# expansion.net
KiCad netlist of a schematic drawn in EAGLE
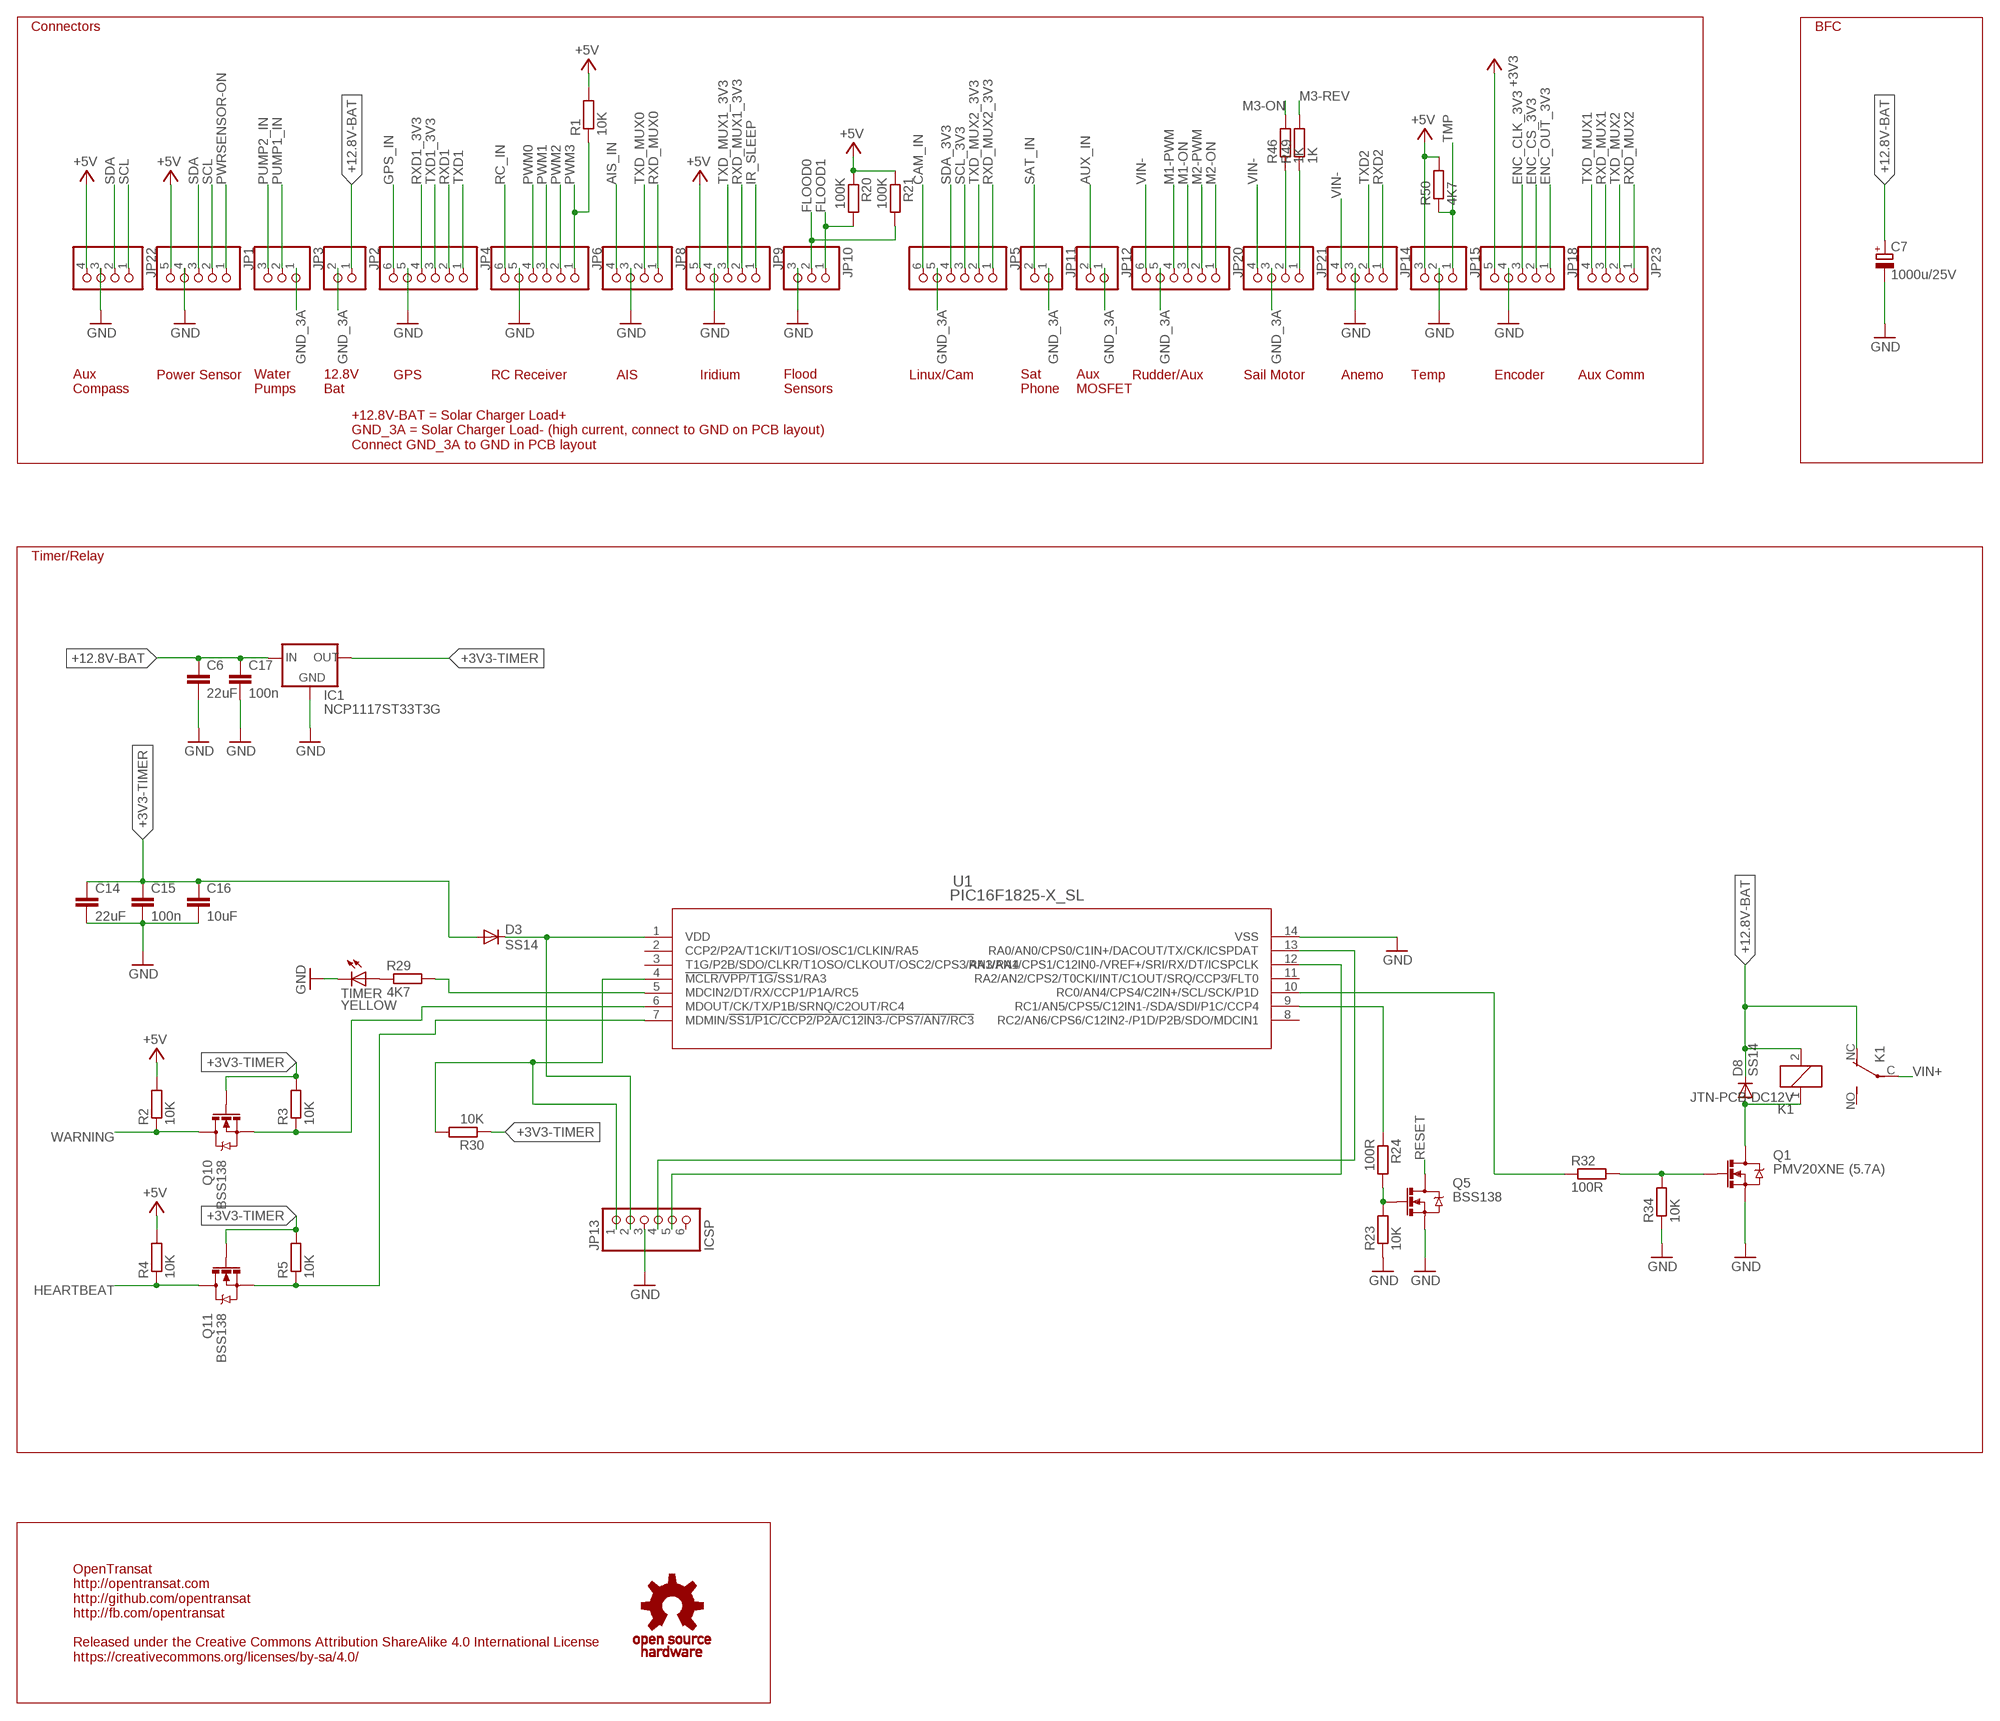
[diagram p0: schematic, sheet 1, part 1 of 2]
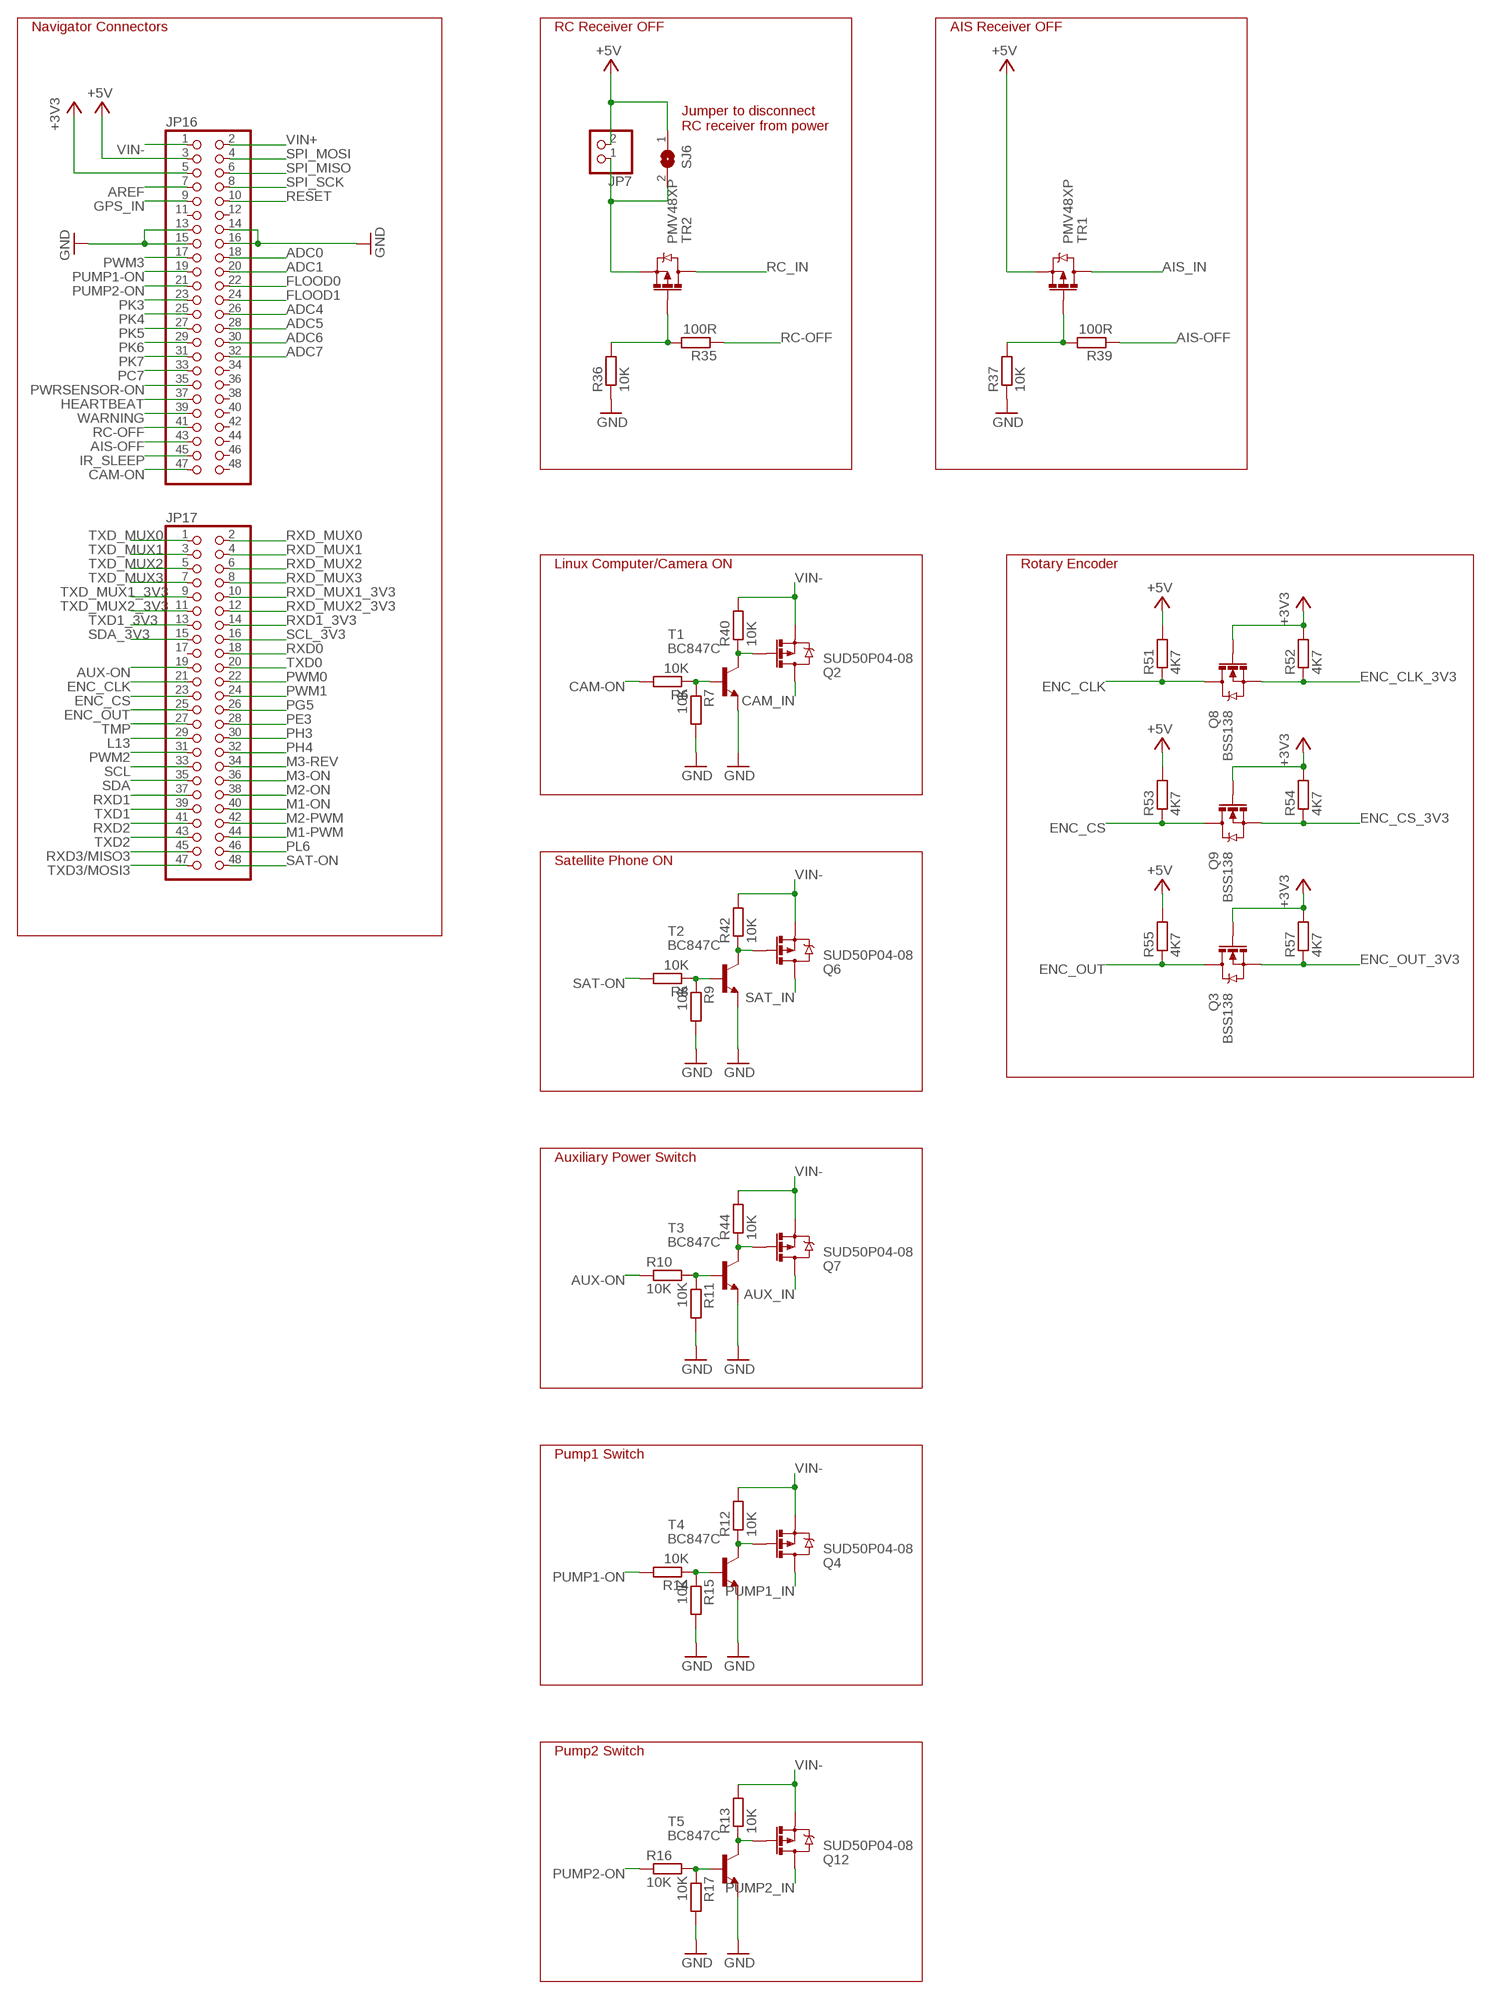
[diagram p1: schematic, sheet 1, part 2 of 2]

(export (version "E")
  (design (tool "Eeschema 10.0.6"))
  (components
    (comp (ref "C6")
      (value "22uF")
      (footprint "eagle-import:C1210")
      (libsource (lib "eagle-import") (part "C-EUC1210"))
    )
    (comp (ref "C7")
      (value "1000u/25V")
      (footprint "eagle-import:E5-10,5")
      (libsource (lib "eagle-import") (part "CPOL-EUE5-10.5"))
    )
    (comp (ref "C14")
      (value "22uF")
      (footprint "eagle-import:C1210")
      (libsource (lib "eagle-import") (part "C-EUC1210"))
    )
    (comp (ref "C15")
      (value "100n")
      (footprint "eagle-import:C0603")
      (libsource (lib "eagle-import") (part "C-EUC0603"))
    )
    (comp (ref "C16")
      (value "10uF")
      (footprint "eagle-import:C1206")
      (libsource (lib "eagle-import") (part "C-EUC1206"))
    )
    (comp (ref "C17")
      (value "100n")
      (footprint "eagle-import:C0603")
      (libsource (lib "eagle-import") (part "C-EUC0603"))
    )
    (comp (ref "D3")
      (value "SS14")
      (footprint "eagle-import:DO214AC")
      (libsource (lib "eagle-import") (part "DIODE-DO214AC"))
    )
    (comp (ref "D8")
      (value "SS14")
      (footprint "eagle-import:DO214AC")
      (libsource (lib "eagle-import") (part "DIODE-DO214AC"))
    )
    (comp (ref "IC1")
      (value "NCP1117ST33T3G")
      (footprint "eagle-import:SOT223")
      (fields (field (name "MF") "Texas Instruments") (field (name "MPN") "LM1117MP-3.3"))
      (libsource (lib "eagle-import") (part "LM1117?-MP3.3"))
    )
    (comp (ref "JP1")
      (value "PINHD-1X5")
      (footprint "eagle-import:1X05")
      (libsource (lib "eagle-import") (part "PINHD-1X5"))
    )
    (comp (ref "JP2")
      (value "PINHD-1X2")
      (footprint "eagle-import:1X02")
      (libsource (lib "eagle-import") (part "PINHD-1X2"))
    )
    (comp (ref "JP3")
      (value "PINHD-1X3")
      (footprint "eagle-import:1X03")
      (libsource (lib "eagle-import") (part "PINHD-1X3"))
    )
    (comp (ref "JP4")
      (value "PINHD-1X6")
      (footprint "eagle-import:1X06")
      (libsource (lib "eagle-import") (part "PINHD-1X6"))
    )
    (comp (ref "JP5")
      (value "PINHD-1X6")
      (footprint "eagle-import:1X06")
      (libsource (lib "eagle-import") (part "PINHD-1X6"))
    )
    (comp (ref "JP6")
      (value "PINHD-1X6")
      (footprint "eagle-import:1X06")
      (libsource (lib "eagle-import") (part "PINHD-1X6"))
    )
    (comp (ref "JP7")
      (value "PINHD-1X2")
      (footprint "eagle-import:1X02")
      (libsource (lib "eagle-import") (part "PINHD-1X2"))
    )
    (comp (ref "JP8")
      (value "PINHD-1X4")
      (footprint "eagle-import:1X04")
      (libsource (lib "eagle-import") (part "PINHD-1X4"))
    )
    (comp (ref "JP9")
      (value "PINHD-1X5")
      (footprint "eagle-import:1X05")
      (libsource (lib "eagle-import") (part "PINHD-1X5"))
    )
    (comp (ref "JP10")
      (value "PINHD-1X3")
      (footprint "eagle-import:1X03")
      (libsource (lib "eagle-import") (part "PINHD-1X3"))
    )
    (comp (ref "JP11")
      (value "PINHD-1X2")
      (footprint "eagle-import:1X02")
      (libsource (lib "eagle-import") (part "PINHD-1X2"))
    )
    (comp (ref "JP12")
      (value "PINHD-1X2")
      (footprint "eagle-import:1X02")
      (libsource (lib "eagle-import") (part "PINHD-1X2"))
    )
    (comp (ref "JP13")
      (value "ICSP")
      (footprint "eagle-import:1X06")
      (libsource (lib "eagle-import") (part "PINHD-1X6"))
    )
    (comp (ref "JP14")
      (value "PINHD-1X4")
      (footprint "eagle-import:1X04")
      (libsource (lib "eagle-import") (part "PINHD-1X4"))
    )
    (comp (ref "JP15")
      (value "PINHD-1X3")
      (footprint "eagle-import:1X03")
      (libsource (lib "eagle-import") (part "PINHD-1X3"))
    )
    (comp (ref "JP16")
      (value "PINHD-2X24")
      (footprint "eagle-import:2X24")
      (libsource (lib "eagle-import") (part "PINHD-2X24"))
    )
    (comp (ref "JP17")
      (value "PINHD-2X24")
      (footprint "eagle-import:2X24")
      (libsource (lib "eagle-import") (part "PINHD-2X24"))
    )
    (comp (ref "JP18")
      (value "PINHD-1X5")
      (footprint "eagle-import:1X05")
      (libsource (lib "eagle-import") (part "PINHD-1X5"))
    )
    (comp (ref "JP20")
      (value "PINHD-1X6")
      (footprint "eagle-import:1X06")
      (libsource (lib "eagle-import") (part "PINHD-1X6"))
    )
    (comp (ref "JP21")
      (value "PINHD-1X4")
      (footprint "eagle-import:1X04")
      (libsource (lib "eagle-import") (part "PINHD-1X4"))
    )
    (comp (ref "JP22")
      (value "PINHD-1X4")
      (footprint "eagle-import:1X04")
      (libsource (lib "eagle-import") (part "PINHD-1X4"))
    )
    (comp (ref "JP23")
      (value "PINHD-1X4")
      (footprint "eagle-import:1X04")
      (libsource (lib "eagle-import") (part "PINHD-1X4"))
    )
    (comp (ref "K1")
      (value "JTN-PCB-DC12V")
      (footprint "eagle-import:JT-PCB")
      (libsource (lib "eagle-import") (part "JT?-N-PCBDC12V"))
    )
    (comp (ref "Q1")
      (value "PMV20XNE (5.7A)")
      (footprint "eagle-import:SOT23-3")
      (libsource (lib "eagle-import") (part "MOSFET-NCHANNEL_SOT23-3"))
    )
    (comp (ref "Q2")
      (value "SUD50P04-08")
      (footprint "eagle-import:D-PAK_TO252AA")
      (libsource (lib "eagle-import") (part "MOSFET-PCHANNEL_D-PAK"))
    )
    (comp (ref "Q3")
      (value "BSS138")
      (footprint "eagle-import:SOT23-3")
      (libsource (lib "eagle-import") (part "MOSFET-NCHANNEL_SOT23-3"))
    )
    (comp (ref "Q4")
      (value "SUD50P04-08")
      (footprint "eagle-import:D-PAK_TO252AA")
      (libsource (lib "eagle-import") (part "MOSFET-PCHANNEL_D-PAK"))
    )
    (comp (ref "Q5")
      (value "BSS138")
      (footprint "eagle-import:SOT23-3")
      (libsource (lib "eagle-import") (part "MOSFET-NCHANNEL_SOT23-3"))
    )
    (comp (ref "Q6")
      (value "SUD50P04-08")
      (footprint "eagle-import:D-PAK_TO252AA")
      (libsource (lib "eagle-import") (part "MOSFET-PCHANNEL_D-PAK"))
    )
    (comp (ref "Q7")
      (value "SUD50P04-08")
      (footprint "eagle-import:D-PAK_TO252AA")
      (libsource (lib "eagle-import") (part "MOSFET-PCHANNEL_D-PAK"))
    )
    (comp (ref "Q8")
      (value "BSS138")
      (footprint "eagle-import:SOT23-3")
      (libsource (lib "eagle-import") (part "MOSFET-NCHANNEL_SOT23-3"))
    )
    (comp (ref "Q9")
      (value "BSS138")
      (footprint "eagle-import:SOT23-3")
      (libsource (lib "eagle-import") (part "MOSFET-NCHANNEL_SOT23-3"))
    )
    (comp (ref "Q10")
      (value "BSS138")
      (footprint "eagle-import:SOT23-3")
      (libsource (lib "eagle-import") (part "MOSFET-NCHANNEL_SOT23-3"))
    )
    (comp (ref "Q11")
      (value "BSS138")
      (footprint "eagle-import:SOT23-3")
      (libsource (lib "eagle-import") (part "MOSFET-NCHANNEL_SOT23-3"))
    )
    (comp (ref "Q12")
      (value "SUD50P04-08")
      (footprint "eagle-import:D-PAK_TO252AA")
      (libsource (lib "eagle-import") (part "MOSFET-PCHANNEL_D-PAK"))
    )
    (comp (ref "R1")
      (value "10K")
      (footprint "eagle-import:R0603")
      (libsource (lib "eagle-import") (part "R-EU_R0603"))
    )
    (comp (ref "R2")
      (value "10K")
      (footprint "eagle-import:R0603")
      (libsource (lib "eagle-import") (part "R-EU_R0603"))
    )
    (comp (ref "R3")
      (value "10K")
      (footprint "eagle-import:R0603")
      (libsource (lib "eagle-import") (part "R-EU_R0603"))
    )
    (comp (ref "R4")
      (value "10K")
      (footprint "eagle-import:R0603")
      (libsource (lib "eagle-import") (part "R-EU_R0603"))
    )
    (comp (ref "R5")
      (value "10K")
      (footprint "eagle-import:R0603")
      (libsource (lib "eagle-import") (part "R-EU_R0603"))
    )
    (comp (ref "R6")
      (value "10K")
      (footprint "eagle-import:R0603")
      (libsource (lib "eagle-import") (part "R-EU_R0603"))
    )
    (comp (ref "R7")
      (value "10K")
      (footprint "eagle-import:R0603")
      (libsource (lib "eagle-import") (part "R-EU_R0603"))
    )
    (comp (ref "R8")
      (value "10K")
      (footprint "eagle-import:R0603")
      (libsource (lib "eagle-import") (part "R-EU_R0603"))
    )
    (comp (ref "R9")
      (value "10K")
      (footprint "eagle-import:R0603")
      (libsource (lib "eagle-import") (part "R-EU_R0603"))
    )
    (comp (ref "R10")
      (value "10K")
      (footprint "eagle-import:R0603")
      (libsource (lib "eagle-import") (part "R-EU_R0603"))
    )
    (comp (ref "R11")
      (value "10K")
      (footprint "eagle-import:R0603")
      (libsource (lib "eagle-import") (part "R-EU_R0603"))
    )
    (comp (ref "R12")
      (value "10K")
      (footprint "eagle-import:R0603")
      (libsource (lib "eagle-import") (part "R-EU_R0603"))
    )
    (comp (ref "R13")
      (value "10K")
      (footprint "eagle-import:R0603")
      (libsource (lib "eagle-import") (part "R-EU_R0603"))
    )
    (comp (ref "R14")
      (value "10K")
      (footprint "eagle-import:R0603")
      (libsource (lib "eagle-import") (part "R-EU_R0603"))
    )
    (comp (ref "R15")
      (value "10K")
      (footprint "eagle-import:R0603")
      (libsource (lib "eagle-import") (part "R-EU_R0603"))
    )
    (comp (ref "R16")
      (value "10K")
      (footprint "eagle-import:R0603")
      (libsource (lib "eagle-import") (part "R-EU_R0603"))
    )
    (comp (ref "R17")
      (value "10K")
      (footprint "eagle-import:R0603")
      (libsource (lib "eagle-import") (part "R-EU_R0603"))
    )
    (comp (ref "R20")
      (value "100K")
      (footprint "eagle-import:R0603")
      (libsource (lib "eagle-import") (part "R-EU_R0603"))
    )
    (comp (ref "R21")
      (value "100K")
      (footprint "eagle-import:R0603")
      (libsource (lib "eagle-import") (part "R-EU_R0603"))
    )
    (comp (ref "R23")
      (value "10K")
      (footprint "eagle-import:R0603")
      (libsource (lib "eagle-import") (part "R-EU_R0603"))
    )
    (comp (ref "R24")
      (value "100R")
      (footprint "eagle-import:R0603")
      (libsource (lib "eagle-import") (part "R-EU_R0603"))
    )
    (comp (ref "R29")
      (value "4K7")
      (footprint "eagle-import:R0603")
      (libsource (lib "eagle-import") (part "R-EU_R0603"))
    )
    (comp (ref "R30")
      (value "10K")
      (footprint "eagle-import:R0603")
      (libsource (lib "eagle-import") (part "R-EU_R0603"))
    )
    (comp (ref "R32")
      (value "100R")
      (footprint "eagle-import:R0603")
      (libsource (lib "eagle-import") (part "R-EU_R0603"))
    )
    (comp (ref "R34")
      (value "10K")
      (footprint "eagle-import:R0603")
      (libsource (lib "eagle-import") (part "R-EU_R0603"))
    )
    (comp (ref "R35")
      (value "100R")
      (footprint "eagle-import:R0603")
      (libsource (lib "eagle-import") (part "R-EU_R0603"))
    )
    (comp (ref "R36")
      (value "10K")
      (footprint "eagle-import:R0603")
      (libsource (lib "eagle-import") (part "R-EU_R0603"))
    )
    (comp (ref "R37")
      (value "10K")
      (footprint "eagle-import:R0603")
      (libsource (lib "eagle-import") (part "R-EU_R0603"))
    )
    (comp (ref "R39")
      (value "100R")
      (footprint "eagle-import:R0603")
      (libsource (lib "eagle-import") (part "R-EU_R0603"))
    )
    (comp (ref "R40")
      (value "10K")
      (footprint "eagle-import:R0603")
      (libsource (lib "eagle-import") (part "R-EU_R0603"))
    )
    (comp (ref "R42")
      (value "10K")
      (footprint "eagle-import:R0603")
      (libsource (lib "eagle-import") (part "R-EU_R0603"))
    )
    (comp (ref "R44")
      (value "10K")
      (footprint "eagle-import:R0603")
      (libsource (lib "eagle-import") (part "R-EU_R0603"))
    )
    (comp (ref "R46")
      (value "1K")
      (footprint "eagle-import:R0603")
      (libsource (lib "eagle-import") (part "R-EU_R0603"))
    )
    (comp (ref "R49")
      (value "1K")
      (footprint "eagle-import:R0603")
      (libsource (lib "eagle-import") (part "R-EU_R0603"))
    )
    (comp (ref "R50")
      (value "4K7")
      (footprint "eagle-import:R0603")
      (libsource (lib "eagle-import") (part "R-EU_R0603"))
    )
    (comp (ref "R51")
      (value "4K7")
      (footprint "eagle-import:R0603")
      (libsource (lib "eagle-import") (part "R-EU_R0603"))
    )
    (comp (ref "R52")
      (value "4K7")
      (footprint "eagle-import:R0603")
      (libsource (lib "eagle-import") (part "R-EU_R0603"))
    )
    (comp (ref "R53")
      (value "4K7")
      (footprint "eagle-import:R0603")
      (libsource (lib "eagle-import") (part "R-EU_R0603"))
    )
    (comp (ref "R54")
      (value "4K7")
      (footprint "eagle-import:R0603")
      (libsource (lib "eagle-import") (part "R-EU_R0603"))
    )
    (comp (ref "R55")
      (value "4K7")
      (footprint "eagle-import:R0603")
      (libsource (lib "eagle-import") (part "R-EU_R0603"))
    )
    (comp (ref "R57")
      (value "4K7")
      (footprint "eagle-import:R0603")
      (libsource (lib "eagle-import") (part "R-EU_R0603"))
    )
    (comp (ref "SJ6") (value "SJ") (footprint "eagle-import:SJ") (libsource (lib "eagle-import") (part "SJ")))
    (comp (ref "T1")
      (value "BC847C")
      (footprint "eagle-import:SOT23")
      (libsource (lib "eagle-import") (part "BC847"))
    )
    (comp (ref "T2")
      (value "BC847C")
      (footprint "eagle-import:SOT23")
      (libsource (lib "eagle-import") (part "BC847"))
    )
    (comp (ref "T3")
      (value "BC847C")
      (footprint "eagle-import:SOT23")
      (libsource (lib "eagle-import") (part "BC847"))
    )
    (comp (ref "T4")
      (value "BC847C")
      (footprint "eagle-import:SOT23")
      (libsource (lib "eagle-import") (part "BC847"))
    )
    (comp (ref "T5")
      (value "BC847C")
      (footprint "eagle-import:SOT23")
      (libsource (lib "eagle-import") (part "BC847"))
    )
    (comp (ref "TIMER")
      (value "YELLOW")
      (footprint "eagle-import:CHIPLED_0805")
      (libsource (lib "eagle-import") (part "LEDCHIPLED_0805"))
    )
    (comp (ref "TR1")
      (value "PMV48XP")
      (footprint "eagle-import:SOT23-3")
      (libsource (lib "eagle-import") (part "MOSFET-PCHANNEL_SOT23-3"))
    )
    (comp (ref "TR2")
      (value "PMV48XP")
      (footprint "eagle-import:SOT23-3")
      (libsource (lib "eagle-import") (part "MOSFET-PCHANNEL_SOT23-3"))
    )
    (comp (ref "U$2")
      (value "OSHW")
      (footprint "eagle-import:OSHWM")
      (libsource (lib "eagle-import") (part "OSHW"))
    )
    (comp (ref "U1")
      (value "PIC16F1825-X_SL")
      (footprint "eagle-import:SOIC14-N_MC")
      (libsource (lib "eagle-import") (part "PIC16F1825-X_SL"))
    )
  )
  (nets
    (net (code "1") (name "+3V3") (class "Default")
      (node (ref "JP16") (pin "5") (pinfunction "5_5") (pintype "passive"))
      (node (ref "JP18") (pin "5") (pinfunction "5_5") (pintype "passive"))
      (node (ref "Q3") (pin "1") (pinfunction "G_1") (pintype "passive"))
      (node (ref "Q8") (pin "1") (pinfunction "G_1") (pintype "passive"))
      (node (ref "Q9") (pin "1") (pinfunction "G_1") (pintype "passive"))
      (node (ref "R52") (pin "2") (pinfunction "2_2") (pintype "passive"))
      (node (ref "R54") (pin "2") (pinfunction "2_2") (pintype "passive"))
      (node (ref "R57") (pin "2") (pinfunction "2_2") (pintype "passive"))
    )
    (net (code "2") (name "+3V3-TIMER") (class "Default")
      (node (ref "C14") (pin "1") (pinfunction "1_1") (pintype "passive"))
      (node (ref "C15") (pin "1") (pinfunction "1_1") (pintype "passive"))
      (node (ref "C16") (pin "1") (pinfunction "1_1") (pintype "passive"))
      (node (ref "D3") (pin "A") (pinfunction "A_A") (pintype "passive"))
      (node (ref "IC1") (pin "2") (pinfunction "OUT_2") (pintype "passive"))
      (node (ref "IC1") (pin "4") (pinfunction "OUT_4") (pintype "passive"))
      (node (ref "Q10") (pin "1") (pinfunction "G_1") (pintype "passive"))
      (node (ref "Q11") (pin "1") (pinfunction "G_1") (pintype "passive"))
      (node (ref "R3") (pin "2") (pinfunction "2_2") (pintype "passive"))
      (node (ref "R30") (pin "1") (pinfunction "1_1") (pintype "passive"))
      (node (ref "R5") (pin "2") (pinfunction "2_2") (pintype "passive"))
    )
    (net (code "3") (name "+5V") (class "Default")
      (node (ref "JP1") (pin "5") (pinfunction "5_5") (pintype "passive"))
      (node (ref "JP15") (pin "3") (pinfunction "3_3") (pintype "passive"))
      (node (ref "JP16") (pin "3") (pinfunction "3_3") (pintype "passive"))
      (node (ref "JP22") (pin "4") (pinfunction "4_4") (pintype "passive"))
      (node (ref "JP7") (pin "2") (pinfunction "2_2") (pintype "passive"))
      (node (ref "JP9") (pin "5") (pinfunction "5_5") (pintype "passive"))
      (node (ref "R1") (pin "2") (pinfunction "2_2") (pintype "passive"))
      (node (ref "R2") (pin "2") (pinfunction "2_2") (pintype "passive"))
      (node (ref "R20") (pin "1") (pinfunction "1_1") (pintype "passive"))
      (node (ref "R21") (pin "1") (pinfunction "1_1") (pintype "passive"))
      (node (ref "R4") (pin "2") (pinfunction "2_2") (pintype "passive"))
      (node (ref "R50") (pin "2") (pinfunction "2_2") (pintype "passive"))
      (node (ref "R51") (pin "2") (pinfunction "2_2") (pintype "passive"))
      (node (ref "R53") (pin "2") (pinfunction "2_2") (pintype "passive"))
      (node (ref "R55") (pin "2") (pinfunction "2_2") (pintype "passive"))
      (node (ref "SJ6") (pin "1") (pinfunction "1_1") (pintype "passive"))
      (node (ref "TR1") (pin "2") (pinfunction "S_2") (pintype "passive"))
    )
    (net (code "4") (name "+12.8V-BAT") (class "Default")
      (node (ref "C17") (pin "1") (pinfunction "1_1") (pintype "passive"))
      (node (ref "C6") (pin "1") (pinfunction "1_1") (pintype "passive"))
      (node (ref "C7") (pin "+") (pinfunction "+_+") (pintype "passive"))
      (node (ref "D8") (pin "C") (pinfunction "C_C") (pintype "passive"))
      (node (ref "IC1") (pin "3") (pinfunction "IN_3") (pintype "input"))
      (node (ref "JP2") (pin "1") (pinfunction "1_1") (pintype "passive"))
      (node (ref "K1") (pin "2") (pinfunction "2_2") (pintype "passive"))
      (node (ref "K1") (pin "NC") (pinfunction "O_NC") (pintype "passive"))
    )
    (net (code "5") (name "/ADC0") (class "Default")
      (node (ref "JP16") (pin "18") (pinfunction "18_18") (pintype "passive"))
    )
    (net (code "6") (name "/ADC1") (class "Default")
      (node (ref "JP16") (pin "20") (pinfunction "20_20") (pintype "passive"))
    )
    (net (code "7") (name "/ADC4") (class "Default")
      (node (ref "JP16") (pin "26") (pinfunction "26_26") (pintype "passive"))
    )
    (net (code "8") (name "/ADC5") (class "Default")
      (node (ref "JP16") (pin "28") (pinfunction "28_28") (pintype "passive"))
    )
    (net (code "9") (name "/ADC6") (class "Default")
      (node (ref "JP16") (pin "30") (pinfunction "30_30") (pintype "passive"))
    )
    (net (code "10") (name "/ADC7") (class "Default")
      (node (ref "JP16") (pin "32") (pinfunction "32_32") (pintype "passive"))
    )
    (net (code "11") (name "/AIS-OFF") (class "Default")
      (node (ref "JP16") (pin "43") (pinfunction "43_43") (pintype "passive"))
      (node (ref "R39") (pin "1") (pinfunction "1_1") (pintype "passive"))
    )
    (net (code "12") (name "/AIS_IN") (class "Default")
      (node (ref "JP8") (pin "4") (pinfunction "4_4") (pintype "passive"))
      (node (ref "TR1") (pin "3") (pinfunction "D_3") (pintype "passive"))
    )
    (net (code "13") (name "/AREF") (class "Default")
      (node (ref "JP16") (pin "7") (pinfunction "7_7") (pintype "passive"))
    )
    (net (code "14") (name "/AUX-ON") (class "Default")
      (node (ref "JP17") (pin "19") (pinfunction "19_19") (pintype "passive"))
      (node (ref "R10") (pin "1") (pinfunction "1_1") (pintype "passive"))
    )
    (net (code "15") (name "/AUX_IN") (class "Default")
      (node (ref "JP12") (pin "2") (pinfunction "2_2") (pintype "passive"))
      (node (ref "Q7") (pin "2") (pinfunction "D_2") (pintype "passive"))
    )
    (net (code "16") (name "/CAM-ON") (class "Default")
      (node (ref "JP16") (pin "47") (pinfunction "47_47") (pintype "passive"))
      (node (ref "R6") (pin "2") (pinfunction "2_2") (pintype "passive"))
    )
    (net (code "17") (name "/CAM_IN") (class "Default")
      (node (ref "JP5") (pin "6") (pinfunction "6_6") (pintype "passive"))
      (node (ref "Q2") (pin "2") (pinfunction "D_2") (pintype "passive"))
    )
    (net (code "18") (name "/ENC_CLK") (class "Default")
      (node (ref "JP17") (pin "21") (pinfunction "21_21") (pintype "passive"))
      (node (ref "Q8") (pin "3") (pinfunction "D_3") (pintype "passive"))
      (node (ref "R51") (pin "1") (pinfunction "1_1") (pintype "passive"))
    )
    (net (code "19") (name "/ENC_CLK_3V3") (class "Default")
      (node (ref "JP18") (pin "3") (pinfunction "3_3") (pintype "passive"))
      (node (ref "Q8") (pin "2") (pinfunction "S_2") (pintype "passive"))
      (node (ref "R52") (pin "1") (pinfunction "1_1") (pintype "passive"))
    )
    (net (code "20") (name "/ENC_CS") (class "Default")
      (node (ref "JP17") (pin "23") (pinfunction "23_23") (pintype "passive"))
      (node (ref "Q9") (pin "3") (pinfunction "D_3") (pintype "passive"))
      (node (ref "R53") (pin "1") (pinfunction "1_1") (pintype "passive"))
    )
    (net (code "21") (name "/ENC_CS_3V3") (class "Default")
      (node (ref "JP18") (pin "2") (pinfunction "2_2") (pintype "passive"))
      (node (ref "Q9") (pin "2") (pinfunction "S_2") (pintype "passive"))
      (node (ref "R54") (pin "1") (pinfunction "1_1") (pintype "passive"))
    )
    (net (code "22") (name "/ENC_OUT") (class "Default")
      (node (ref "JP17") (pin "25") (pinfunction "25_25") (pintype "passive"))
      (node (ref "Q3") (pin "3") (pinfunction "D_3") (pintype "passive"))
      (node (ref "R55") (pin "1") (pinfunction "1_1") (pintype "passive"))
    )
    (net (code "23") (name "/ENC_OUT_3V3") (class "Default")
      (node (ref "JP18") (pin "1") (pinfunction "1_1") (pintype "passive"))
      (node (ref "Q3") (pin "2") (pinfunction "S_2") (pintype "passive"))
      (node (ref "R57") (pin "1") (pinfunction "1_1") (pintype "passive"))
    )
    (net (code "24") (name "/FLOOD0") (class "Default")
      (node (ref "JP10") (pin "2") (pinfunction "2_2") (pintype "passive"))
      (node (ref "JP16") (pin "22") (pinfunction "22_22") (pintype "passive"))
      (node (ref "R21") (pin "2") (pinfunction "2_2") (pintype "passive"))
    )
    (net (code "25") (name "/FLOOD1") (class "Default")
      (node (ref "JP10") (pin "1") (pinfunction "1_1") (pintype "passive"))
      (node (ref "JP16") (pin "24") (pinfunction "24_24") (pintype "passive"))
      (node (ref "R20") (pin "2") (pinfunction "2_2") (pintype "passive"))
    )
    (net (code "26") (name "/GND_3A") (class "Default")
      (node (ref "JP11") (pin "1") (pinfunction "1_1") (pintype "passive"))
      (node (ref "JP12") (pin "1") (pinfunction "1_1") (pintype "passive"))
      (node (ref "JP2") (pin "2") (pinfunction "2_2") (pintype "passive"))
      (node (ref "JP20") (pin "5") (pinfunction "5_5") (pintype "passive"))
      (node (ref "JP21") (pin "3") (pinfunction "3_3") (pintype "passive"))
      (node (ref "JP3") (pin "1") (pinfunction "1_1") (pintype "passive"))
      (node (ref "JP5") (pin "5") (pinfunction "5_5") (pintype "passive"))
    )
    (net (code "27") (name "/GPS_IN") (class "Default")
      (node (ref "JP16") (pin "9") (pinfunction "9_9") (pintype "passive"))
      (node (ref "JP4") (pin "6") (pinfunction "6_6") (pintype "passive"))
    )
    (net (code "28") (name "/HEARTBEAT") (class "Default")
      (node (ref "JP16") (pin "37") (pinfunction "37_37") (pintype "passive"))
      (node (ref "Q11") (pin "3") (pinfunction "D_3") (pintype "passive"))
      (node (ref "R4") (pin "1") (pinfunction "1_1") (pintype "passive"))
    )
    (net (code "29") (name "/IR_SLEEP") (class "Default")
      (node (ref "JP16") (pin "45") (pinfunction "45_45") (pintype "passive"))
      (node (ref "JP9") (pin "1") (pinfunction "1_1") (pintype "passive"))
    )
    (net (code "30") (name "/L13") (class "Default")
      (node (ref "JP17") (pin "29") (pinfunction "29_29") (pintype "passive"))
    )
    (net (code "31") (name "/M1-ON") (class "Default")
      (node (ref "JP17") (pin "40") (pinfunction "40_40") (pintype "passive"))
      (node (ref "JP20") (pin "3") (pinfunction "3_3") (pintype "passive"))
    )
    (net (code "32") (name "/M1-PWM") (class "Default")
      (node (ref "JP17") (pin "44") (pinfunction "44_44") (pintype "passive"))
      (node (ref "JP20") (pin "4") (pinfunction "4_4") (pintype "passive"))
    )
    (net (code "33") (name "/M2-ON") (class "Default")
      (node (ref "JP17") (pin "38") (pinfunction "38_38") (pintype "passive"))
      (node (ref "JP20") (pin "1") (pinfunction "1_1") (pintype "passive"))
    )
    (net (code "34") (name "/M2-PWM") (class "Default")
      (node (ref "JP17") (pin "42") (pinfunction "42_42") (pintype "passive"))
      (node (ref "JP20") (pin "2") (pinfunction "2_2") (pintype "passive"))
    )
    (net (code "35") (name "/M3-ON") (class "Default")
      (node (ref "JP17") (pin "36") (pinfunction "36_36") (pintype "passive"))
      (node (ref "R46") (pin "2") (pinfunction "2_2") (pintype "passive"))
    )
    (net (code "36") (name "/M3-REV") (class "Default")
      (node (ref "JP17") (pin "34") (pinfunction "34_34") (pintype "passive"))
      (node (ref "R49") (pin "2") (pinfunction "2_2") (pintype "passive"))
    )
    (net (code "37") (name "/PC7") (class "Default")
      (node (ref "JP16") (pin "33") (pinfunction "33_33") (pintype "passive"))
    )
    (net (code "38") (name "/PE3") (class "Default")
      (node (ref "JP17") (pin "28") (pinfunction "28_28") (pintype "passive"))
    )
    (net (code "39") (name "/PG5") (class "Default")
      (node (ref "JP17") (pin "26") (pinfunction "26_26") (pintype "passive"))
    )
    (net (code "40") (name "/PH3") (class "Default")
      (node (ref "JP17") (pin "30") (pinfunction "30_30") (pintype "passive"))
    )
    (net (code "41") (name "/PH4") (class "Default")
      (node (ref "JP17") (pin "32") (pinfunction "32_32") (pintype "passive"))
    )
    (net (code "42") (name "/PK3") (class "Default")
      (node (ref "JP16") (pin "23") (pinfunction "23_23") (pintype "passive"))
    )
    (net (code "43") (name "/PK4") (class "Default")
      (node (ref "JP16") (pin "25") (pinfunction "25_25") (pintype "passive"))
    )
    (net (code "44") (name "/PK5") (class "Default")
      (node (ref "JP16") (pin "27") (pinfunction "27_27") (pintype "passive"))
    )
    (net (code "45") (name "/PK6") (class "Default")
      (node (ref "JP16") (pin "29") (pinfunction "29_29") (pintype "passive"))
    )
    (net (code "46") (name "/PK7") (class "Default")
      (node (ref "JP16") (pin "31") (pinfunction "31_31") (pintype "passive"))
    )
    (net (code "47") (name "/PL6") (class "Default")
      (node (ref "JP17") (pin "46") (pinfunction "46_46") (pintype "passive"))
    )
    (net (code "48") (name "/PUMP1-ON") (class "Default")
      (node (ref "JP16") (pin "19") (pinfunction "19_19") (pintype "passive"))
      (node (ref "R14") (pin "2") (pinfunction "2_2") (pintype "passive"))
    )
    (net (code "49") (name "/PUMP1_IN") (class "Default")
      (node (ref "JP3") (pin "2") (pinfunction "2_2") (pintype "passive"))
      (node (ref "Q4") (pin "2") (pinfunction "D_2") (pintype "passive"))
    )
    (net (code "50") (name "/PUMP2-ON") (class "Default")
      (node (ref "JP16") (pin "21") (pinfunction "21_21") (pintype "passive"))
      (node (ref "R16") (pin "1") (pinfunction "1_1") (pintype "passive"))
    )
    (net (code "51") (name "/PUMP2_IN") (class "Default")
      (node (ref "JP3") (pin "3") (pinfunction "3_3") (pintype "passive"))
      (node (ref "Q12") (pin "2") (pinfunction "D_2") (pintype "passive"))
    )
    (net (code "52") (name "/PWM0") (class "Default")
      (node (ref "JP17") (pin "22") (pinfunction "22_22") (pintype "passive"))
      (node (ref "JP6") (pin "4") (pinfunction "4_4") (pintype "passive"))
    )
    (net (code "53") (name "/PWM1") (class "Default")
      (node (ref "JP17") (pin "24") (pinfunction "24_24") (pintype "passive"))
      (node (ref "JP6") (pin "3") (pinfunction "3_3") (pintype "passive"))
    )
    (net (code "54") (name "/PWM2") (class "Default")
      (node (ref "JP17") (pin "31") (pinfunction "31_31") (pintype "passive"))
      (node (ref "JP6") (pin "2") (pinfunction "2_2") (pintype "passive"))
    )
    (net (code "55") (name "/PWM3") (class "Default")
      (node (ref "JP16") (pin "17") (pinfunction "17_17") (pintype "passive"))
      (node (ref "JP6") (pin "1") (pinfunction "1_1") (pintype "passive"))
      (node (ref "R1") (pin "1") (pinfunction "1_1") (pintype "passive"))
    )
    (net (code "56") (name "/PWRSENSOR-ON") (class "Default")
      (node (ref "JP1") (pin "1") (pinfunction "1_1") (pintype "passive"))
      (node (ref "JP16") (pin "35") (pinfunction "35_35") (pintype "passive"))
    )
    (net (code "57") (name "/RC-OFF") (class "Default")
      (node (ref "JP16") (pin "41") (pinfunction "41_41") (pintype "passive"))
      (node (ref "R35") (pin "1") (pinfunction "1_1") (pintype "passive"))
    )
    (net (code "58") (name "/RC_IN") (class "Default")
      (node (ref "JP6") (pin "6") (pinfunction "6_6") (pintype "passive"))
      (node (ref "TR2") (pin "3") (pinfunction "D_3") (pintype "passive"))
    )
    (net (code "59") (name "/RESET") (class "Default")
      (node (ref "JP16") (pin "10") (pinfunction "10_10") (pintype "passive"))
      (node (ref "Q5") (pin "3") (pinfunction "D_3") (pintype "passive"))
    )
    (net (code "60") (name "/RXD0") (class "Default")
      (node (ref "JP17") (pin "18") (pinfunction "18_18") (pintype "passive"))
    )
    (net (code "61") (name "/RXD1") (class "Default")
      (node (ref "JP17") (pin "37") (pinfunction "37_37") (pintype "passive"))
      (node (ref "JP4") (pin "2") (pinfunction "2_2") (pintype "passive"))
    )
    (net (code "62") (name "/RXD1_3V3") (class "Default")
      (node (ref "JP17") (pin "14") (pinfunction "14_14") (pintype "passive"))
      (node (ref "JP4") (pin "4") (pinfunction "4_4") (pintype "passive"))
    )
    (net (code "63") (name "/RXD2") (class "Default")
      (node (ref "JP14") (pin "1") (pinfunction "1_1") (pintype "passive"))
      (node (ref "JP17") (pin "41") (pinfunction "41_41") (pintype "passive"))
    )
    (net (code "64") (name "/RXD3{slash}MISO3") (class "Default")
      (node (ref "JP17") (pin "45") (pinfunction "45_45") (pintype "passive"))
    )
    (net (code "65") (name "/RXD_MUX0") (class "Default")
      (node (ref "JP17") (pin "2") (pinfunction "2_2") (pintype "passive"))
      (node (ref "JP8") (pin "1") (pinfunction "1_1") (pintype "passive"))
    )
    (net (code "66") (name "/RXD_MUX1") (class "Default")
      (node (ref "JP17") (pin "4") (pinfunction "4_4") (pintype "passive"))
      (node (ref "JP23") (pin "3") (pinfunction "3_3") (pintype "passive"))
    )
    (net (code "67") (name "/RXD_MUX1_3V3") (class "Default")
      (node (ref "JP17") (pin "10") (pinfunction "10_10") (pintype "passive"))
      (node (ref "JP9") (pin "2") (pinfunction "2_2") (pintype "passive"))
    )
    (net (code "68") (name "/RXD_MUX2") (class "Default")
      (node (ref "JP17") (pin "6") (pinfunction "6_6") (pintype "passive"))
      (node (ref "JP23") (pin "1") (pinfunction "1_1") (pintype "passive"))
    )
    (net (code "69") (name "/RXD_MUX2_3V3") (class "Default")
      (node (ref "JP17") (pin "12") (pinfunction "12_12") (pintype "passive"))
      (node (ref "JP5") (pin "1") (pinfunction "1_1") (pintype "passive"))
    )
    (net (code "70") (name "/RXD_MUX3") (class "Default")
      (node (ref "JP17") (pin "8") (pinfunction "8_8") (pintype "passive"))
    )
    (net (code "71") (name "/SAT-ON") (class "Default")
      (node (ref "JP17") (pin "48") (pinfunction "48_48") (pintype "passive"))
      (node (ref "R8") (pin "2") (pinfunction "2_2") (pintype "passive"))
    )
    (net (code "72") (name "/SAT_IN") (class "Default")
      (node (ref "JP11") (pin "2") (pinfunction "2_2") (pintype "passive"))
      (node (ref "Q6") (pin "2") (pinfunction "D_2") (pintype "passive"))
    )
    (net (code "73") (name "/SCL") (class "Default")
      (node (ref "JP1") (pin "2") (pinfunction "2_2") (pintype "passive"))
      (node (ref "JP17") (pin "33") (pinfunction "33_33") (pintype "passive"))
      (node (ref "JP22") (pin "1") (pinfunction "1_1") (pintype "passive"))
    )
    (net (code "74") (name "/SCL_3V3") (class "Default")
      (node (ref "JP17") (pin "16") (pinfunction "16_16") (pintype "passive"))
      (node (ref "JP5") (pin "3") (pinfunction "3_3") (pintype "passive"))
    )
    (net (code "75") (name "/SDA") (class "Default")
      (node (ref "JP1") (pin "3") (pinfunction "3_3") (pintype "passive"))
      (node (ref "JP17") (pin "35") (pinfunction "35_35") (pintype "passive"))
      (node (ref "JP22") (pin "2") (pinfunction "2_2") (pintype "passive"))
    )
    (net (code "76") (name "/SDA_3V3") (class "Default")
      (node (ref "JP17") (pin "15") (pinfunction "15_15") (pintype "passive"))
      (node (ref "JP5") (pin "4") (pinfunction "4_4") (pintype "passive"))
    )
    (net (code "77") (name "/SPI_MISO") (class "Default")
      (node (ref "JP16") (pin "6") (pinfunction "6_6") (pintype "passive"))
    )
    (net (code "78") (name "/SPI_MOSI") (class "Default")
      (node (ref "JP16") (pin "4") (pinfunction "4_4") (pintype "passive"))
    )
    (net (code "79") (name "/SPI_SCK") (class "Default")
      (node (ref "JP16") (pin "8") (pinfunction "8_8") (pintype "passive"))
    )
    (net (code "80") (name "/TMP") (class "Default")
      (node (ref "JP15") (pin "1") (pinfunction "1_1") (pintype "passive"))
      (node (ref "JP17") (pin "27") (pinfunction "27_27") (pintype "passive"))
      (node (ref "R50") (pin "1") (pinfunction "1_1") (pintype "passive"))
    )
    (net (code "81") (name "/TXD0") (class "Default")
      (node (ref "JP17") (pin "20") (pinfunction "20_20") (pintype "passive"))
    )
    (net (code "82") (name "/TXD1") (class "Default")
      (node (ref "JP17") (pin "39") (pinfunction "39_39") (pintype "passive"))
      (node (ref "JP4") (pin "1") (pinfunction "1_1") (pintype "passive"))
    )
    (net (code "83") (name "/TXD1_3V3") (class "Default")
      (node (ref "JP17") (pin "13") (pinfunction "13_13") (pintype "passive"))
      (node (ref "JP4") (pin "3") (pinfunction "3_3") (pintype "passive"))
    )
    (net (code "84") (name "/TXD2") (class "Default")
      (node (ref "JP14") (pin "2") (pinfunction "2_2") (pintype "passive"))
      (node (ref "JP17") (pin "43") (pinfunction "43_43") (pintype "passive"))
    )
    (net (code "85") (name "/TXD3{slash}MOSI3") (class "Default")
      (node (ref "JP17") (pin "47") (pinfunction "47_47") (pintype "passive"))
    )
    (net (code "86") (name "/TXD_MUX0") (class "Default")
      (node (ref "JP17") (pin "1") (pinfunction "1_1") (pintype "passive"))
      (node (ref "JP8") (pin "2") (pinfunction "2_2") (pintype "passive"))
    )
    (net (code "87") (name "/TXD_MUX1") (class "Default")
      (node (ref "JP17") (pin "3") (pinfunction "3_3") (pintype "passive"))
      (node (ref "JP23") (pin "4") (pinfunction "4_4") (pintype "passive"))
    )
    (net (code "88") (name "/TXD_MUX1_3V3") (class "Default")
      (node (ref "JP17") (pin "9") (pinfunction "9_9") (pintype "passive"))
      (node (ref "JP9") (pin "3") (pinfunction "3_3") (pintype "passive"))
    )
    (net (code "89") (name "/TXD_MUX2") (class "Default")
      (node (ref "JP17") (pin "5") (pinfunction "5_5") (pintype "passive"))
      (node (ref "JP23") (pin "2") (pinfunction "2_2") (pintype "passive"))
    )
    (net (code "90") (name "/TXD_MUX2_3V3") (class "Default")
      (node (ref "JP17") (pin "11") (pinfunction "11_11") (pintype "passive"))
      (node (ref "JP5") (pin "2") (pinfunction "2_2") (pintype "passive"))
    )
    (net (code "91") (name "/TXD_MUX3") (class "Default")
      (node (ref "JP17") (pin "7") (pinfunction "7_7") (pintype "passive"))
    )
    (net (code "92") (name "/VIN+") (class "Default")
      (node (ref "JP16") (pin "2") (pinfunction "2_2") (pintype "passive"))
      (node (ref "K1") (pin "C") (pinfunction "P_C") (pintype "passive"))
    )
    (net (code "93") (name "/VIN-") (class "Default")
      (node (ref "JP14") (pin "4") (pinfunction "4_4") (pintype "passive"))
      (node (ref "JP16") (pin "1") (pinfunction "1_1") (pintype "passive"))
      (node (ref "JP20") (pin "6") (pinfunction "6_6") (pintype "passive"))
      (node (ref "JP21") (pin "4") (pinfunction "4_4") (pintype "passive"))
      (node (ref "Q12") (pin "3") (pinfunction "S_3") (pintype "passive"))
      (node (ref "Q2") (pin "3") (pinfunction "S_3") (pintype "passive"))
      (node (ref "Q4") (pin "3") (pinfunction "S_3") (pintype "passive"))
      (node (ref "Q6") (pin "3") (pinfunction "S_3") (pintype "passive"))
      (node (ref "Q7") (pin "3") (pinfunction "S_3") (pintype "passive"))
      (node (ref "R12") (pin "2") (pinfunction "2_2") (pintype "passive"))
      (node (ref "R13") (pin "2") (pinfunction "2_2") (pintype "passive"))
      (node (ref "R40") (pin "2") (pinfunction "2_2") (pintype "passive"))
      (node (ref "R42") (pin "2") (pinfunction "2_2") (pintype "passive"))
      (node (ref "R44") (pin "2") (pinfunction "2_2") (pintype "passive"))
    )
    (net (code "94") (name "/WARNING") (class "Default")
      (node (ref "JP16") (pin "39") (pinfunction "39_39") (pintype "passive"))
      (node (ref "Q10") (pin "3") (pinfunction "D_3") (pintype "passive"))
      (node (ref "R2") (pin "1") (pinfunction "1_1") (pintype "passive"))
    )
    (net (code "95") (name "GND") (class "Default")
      (node (ref "C14") (pin "2") (pinfunction "2_2") (pintype "passive"))
      (node (ref "C15") (pin "2") (pinfunction "2_2") (pintype "passive"))
      (node (ref "C16") (pin "2") (pinfunction "2_2") (pintype "passive"))
      (node (ref "C17") (pin "2") (pinfunction "2_2") (pintype "passive"))
      (node (ref "C6") (pin "2") (pinfunction "2_2") (pintype "passive"))
      (node (ref "C7") (pin "-") (pinfunction "-_-") (pintype "passive"))
      (node (ref "IC1") (pin "1") (pinfunction "GND_1") (pintype "input"))
      (node (ref "JP1") (pin "4") (pinfunction "4_4") (pintype "passive"))
      (node (ref "JP10") (pin "3") (pinfunction "3_3") (pintype "passive"))
      (node (ref "JP13") (pin "3") (pinfunction "3_3") (pintype "passive"))
      (node (ref "JP14") (pin "3") (pinfunction "3_3") (pintype "passive"))
      (node (ref "JP15") (pin "2") (pinfunction "2_2") (pintype "passive"))
      (node (ref "JP16") (pin "13") (pinfunction "13_13") (pintype "passive"))
      (node (ref "JP16") (pin "14") (pinfunction "14_14") (pintype "passive"))
      (node (ref "JP16") (pin "15") (pinfunction "15_15") (pintype "passive"))
      (node (ref "JP16") (pin "16") (pinfunction "16_16") (pintype "passive"))
      (node (ref "JP18") (pin "4") (pinfunction "4_4") (pintype "passive"))
      (node (ref "JP22") (pin "3") (pinfunction "3_3") (pintype "passive"))
      (node (ref "JP4") (pin "5") (pinfunction "5_5") (pintype "passive"))
      (node (ref "JP6") (pin "5") (pinfunction "5_5") (pintype "passive"))
      (node (ref "JP8") (pin "3") (pinfunction "3_3") (pintype "passive"))
      (node (ref "JP9") (pin "4") (pinfunction "4_4") (pintype "passive"))
      (node (ref "Q1") (pin "2") (pinfunction "S_2") (pintype "passive"))
      (node (ref "Q5") (pin "2") (pinfunction "S_2") (pintype "passive"))
      (node (ref "R11") (pin "2") (pinfunction "2_2") (pintype "passive"))
      (node (ref "R15") (pin "2") (pinfunction "2_2") (pintype "passive"))
      (node (ref "R17") (pin "2") (pinfunction "2_2") (pintype "passive"))
      (node (ref "R23") (pin "1") (pinfunction "1_1") (pintype "passive"))
      (node (ref "R34") (pin "1") (pinfunction "1_1") (pintype "passive"))
      (node (ref "R36") (pin "1") (pinfunction "1_1") (pintype "passive"))
      (node (ref "R37") (pin "1") (pinfunction "1_1") (pintype "passive"))
      (node (ref "R7") (pin "2") (pinfunction "2_2") (pintype "passive"))
      (node (ref "R9") (pin "2") (pinfunction "2_2") (pintype "passive"))
      (node (ref "T1") (pin "2") (pinfunction "E_2") (pintype "passive"))
      (node (ref "T2") (pin "2") (pinfunction "E_2") (pintype "passive"))
      (node (ref "T3") (pin "2") (pinfunction "E_2") (pintype "passive"))
      (node (ref "T4") (pin "2") (pinfunction "E_2") (pintype "passive"))
      (node (ref "T5") (pin "2") (pinfunction "E_2") (pintype "passive"))
      (node (ref "TIMER") (pin "C") (pinfunction "C_C") (pintype "passive"))
      (node (ref "U1") (pin "14") (pinfunction "VSS_14") (pintype "power_in"))
    )
    (net (code "96") (name "Net-(JP21-Pad1)") (class "Default")
      (node (ref "JP21") (pin "1") (pinfunction "1_1") (pintype "passive"))
      (node (ref "R49") (pin "1") (pinfunction "1_1") (pintype "passive"))
    )
    (net (code "97") (name "Net-(JP21-Pad2)") (class "Default")
      (node (ref "JP21") (pin "2") (pinfunction "2_2") (pintype "passive"))
      (node (ref "R46") (pin "1") (pinfunction "1_1") (pintype "passive"))
    )
    (net (code "98") (name "Net-(Q1-D)") (class "Default")
      (node (ref "D8") (pin "A") (pinfunction "A_A") (pintype "passive"))
      (node (ref "K1") (pin "1") (pinfunction "1_1") (pintype "passive"))
      (node (ref "Q1") (pin "3") (pinfunction "D_3") (pintype "passive"))
    )
    (net (code "99") (name "Net-(Q1-G)") (class "Default")
      (node (ref "Q1") (pin "1") (pinfunction "G_1") (pintype "passive"))
      (node (ref "R32") (pin "2") (pinfunction "2_2") (pintype "passive"))
      (node (ref "R34") (pin "2") (pinfunction "2_2") (pintype "passive"))
    )
    (net (code "100") (name "Net-(Q2-G)") (class "Default")
      (node (ref "Q2") (pin "1") (pinfunction "G_1") (pintype "passive"))
      (node (ref "R40") (pin "1") (pinfunction "1_1") (pintype "passive"))
      (node (ref "T1") (pin "3") (pinfunction "C_3") (pintype "passive"))
    )
    (net (code "101") (name "Net-(Q4-G)") (class "Default")
      (node (ref "Q4") (pin "1") (pinfunction "G_1") (pintype "passive"))
      (node (ref "R12") (pin "1") (pinfunction "1_1") (pintype "passive"))
      (node (ref "T4") (pin "3") (pinfunction "C_3") (pintype "passive"))
    )
    (net (code "102") (name "Net-(Q5-G)") (class "Default")
      (node (ref "Q5") (pin "1") (pinfunction "G_1") (pintype "passive"))
      (node (ref "R23") (pin "2") (pinfunction "2_2") (pintype "passive"))
      (node (ref "R24") (pin "2") (pinfunction "2_2") (pintype "passive"))
    )
    (net (code "103") (name "Net-(Q6-G)") (class "Default")
      (node (ref "Q6") (pin "1") (pinfunction "G_1") (pintype "passive"))
      (node (ref "R42") (pin "1") (pinfunction "1_1") (pintype "passive"))
      (node (ref "T2") (pin "3") (pinfunction "C_3") (pintype "passive"))
    )
    (net (code "104") (name "Net-(Q7-G)") (class "Default")
      (node (ref "Q7") (pin "1") (pinfunction "G_1") (pintype "passive"))
      (node (ref "R44") (pin "1") (pinfunction "1_1") (pintype "passive"))
      (node (ref "T3") (pin "3") (pinfunction "C_3") (pintype "passive"))
    )
    (net (code "105") (name "Net-(Q10-S)") (class "Default")
      (node (ref "Q10") (pin "2") (pinfunction "S_2") (pintype "passive"))
      (node (ref "R3") (pin "1") (pinfunction "1_1") (pintype "passive"))
      (node (ref "U1") (pin "6") (pinfunction "MDOUT/CK/TX/P1B/SRNQ/C2OUT/RC4_6") (pintype "bidirectional"))
    )
    (net (code "106") (name "Net-(Q11-S)") (class "Default")
      (node (ref "Q11") (pin "2") (pinfunction "S_2") (pintype "passive"))
      (node (ref "R5") (pin "1") (pinfunction "1_1") (pintype "passive"))
      (node (ref "U1") (pin "7") (pinfunction "MDMIN/~{SS1/P1C/CCP2/P2A/C12IN3-/CPS7/AN7/RC3}_7") (pintype "bidirectional"))
    )
    (net (code "107") (name "Net-(Q12-G)") (class "Default")
      (node (ref "Q12") (pin "1") (pinfunction "G_1") (pintype "passive"))
      (node (ref "R13") (pin "1") (pinfunction "1_1") (pintype "passive"))
      (node (ref "T5") (pin "3") (pinfunction "C_3") (pintype "passive"))
    )
    (net (code "108") (name "Net-(R29-Pad1)") (class "Default")
      (node (ref "R29") (pin "1") (pinfunction "1_1") (pintype "passive"))
      (node (ref "TIMER") (pin "A") (pinfunction "A_A") (pintype "passive"))
    )
    (net (code "109") (name "Net-(T1-B)") (class "Default")
      (node (ref "R6") (pin "1") (pinfunction "1_1") (pintype "passive"))
      (node (ref "R7") (pin "1") (pinfunction "1_1") (pintype "passive"))
      (node (ref "T1") (pin "1") (pinfunction "B_1") (pintype "passive"))
    )
    (net (code "110") (name "Net-(T2-B)") (class "Default")
      (node (ref "R8") (pin "1") (pinfunction "1_1") (pintype "passive"))
      (node (ref "R9") (pin "1") (pinfunction "1_1") (pintype "passive"))
      (node (ref "T2") (pin "1") (pinfunction "B_1") (pintype "passive"))
    )
    (net (code "111") (name "Net-(T3-B)") (class "Default")
      (node (ref "R10") (pin "2") (pinfunction "2_2") (pintype "passive"))
      (node (ref "R11") (pin "1") (pinfunction "1_1") (pintype "passive"))
      (node (ref "T3") (pin "1") (pinfunction "B_1") (pintype "passive"))
    )
    (net (code "112") (name "Net-(T4-B)") (class "Default")
      (node (ref "R14") (pin "1") (pinfunction "1_1") (pintype "passive"))
      (node (ref "R15") (pin "1") (pinfunction "1_1") (pintype "passive"))
      (node (ref "T4") (pin "1") (pinfunction "B_1") (pintype "passive"))
    )
    (net (code "113") (name "Net-(T5-B)") (class "Default")
      (node (ref "R16") (pin "2") (pinfunction "2_2") (pintype "passive"))
      (node (ref "R17") (pin "1") (pinfunction "1_1") (pintype "passive"))
      (node (ref "T5") (pin "1") (pinfunction "B_1") (pintype "passive"))
    )
    (net (code "114") (name "Net-(TR1-G)") (class "Default")
      (node (ref "R37") (pin "2") (pinfunction "2_2") (pintype "passive"))
      (node (ref "R39") (pin "2") (pinfunction "2_2") (pintype "passive"))
      (node (ref "TR1") (pin "1") (pinfunction "G_1") (pintype "passive"))
    )
    (net (code "115") (name "Net-(TR2-G)") (class "Default")
      (node (ref "R35") (pin "2") (pinfunction "2_2") (pintype "passive"))
      (node (ref "R36") (pin "2") (pinfunction "2_2") (pintype "passive"))
      (node (ref "TR2") (pin "1") (pinfunction "G_1") (pintype "passive"))
    )
    (net (code "116") (name "Net-(TR2-S)") (class "Default")
      (node (ref "JP7") (pin "1") (pinfunction "1_1") (pintype "passive"))
      (node (ref "SJ6") (pin "2") (pinfunction "2_2") (pintype "passive"))
      (node (ref "TR2") (pin "2") (pinfunction "S_2") (pintype "passive"))
    )
    (net (code "117") (name "Net-(U1-MDCIN2{slash}DT{slash}RX{slash}CCP1{slash}P1A{slash}RC5)") (class "Default")
      (node (ref "R29") (pin "2") (pinfunction "2_2") (pintype "passive"))
      (node (ref "U1") (pin "5") (pinfunction "MDCIN2/DT/RX/CCP1/P1A/RC5_5") (pintype "bidirectional"))
    )
    (net (code "118") (name "Net-(U1-RA0{slash}AN0{slash}CPS0{slash}C1IN+{slash}DACOUT{slash}TX{slash}CK{slash}ICSPDAT)") (class "Default")
      (node (ref "JP13") (pin "4") (pinfunction "4_4") (pintype "passive"))
      (node (ref "U1") (pin "13") (pinfunction "RA0/AN0/CPS0/C1IN+/DACOUT/TX/CK/ICSPDAT_13") (pintype "bidirectional"))
    )
    (net (code "119") (name "Net-(U1-RA1{slash}AN1{slash}CPS1{slash}C12IN0-{slash}VREF+{slash}SRI{slash}RX{slash}DT{slash}ICSPCLK)") (class "Default")
      (node (ref "JP13") (pin "5") (pinfunction "5_5") (pintype "passive"))
      (node (ref "U1") (pin "12") (pinfunction "RA1/AN1/CPS1/C12IN0-/VREF+/SRI/RX/DT/ICSPCLK_12") (pintype "bidirectional"))
    )
    (net (code "120") (name "Net-(U1-RC0{slash}AN4{slash}CPS4{slash}C2IN+{slash}SCL{slash}SCK{slash}P1D)") (class "Default")
      (node (ref "R32") (pin "1") (pinfunction "1_1") (pintype "passive"))
      (node (ref "U1") (pin "10") (pinfunction "RC0/AN4/CPS4/C2IN+/SCL/SCK/P1D_10") (pintype "bidirectional"))
    )
    (net (code "121") (name "Net-(U1-RC1{slash}AN5{slash}CPS5{slash}C12IN1-{slash}SDA{slash}SDI{slash}P1C{slash}CCP4)") (class "Default")
      (node (ref "R24") (pin "1") (pinfunction "1_1") (pintype "passive"))
      (node (ref "U1") (pin "9") (pinfunction "RC1/AN5/CPS5/C12IN1-/SDA/SDI/P1C/CCP4_9") (pintype "bidirectional"))
    )
    (net (code "122") (name "Net-(U1-VDD)") (class "Default")
      (node (ref "D3") (pin "C") (pinfunction "C_C") (pintype "passive"))
      (node (ref "JP13") (pin "2") (pinfunction "2_2") (pintype "passive"))
      (node (ref "U1") (pin "1") (pinfunction "VDD_1") (pintype "power_in"))
    )
    (net (code "123") (name "Net-(U1-~{MCLR{slash}VPP{slash}T1G{slash}}SS1{slash}RA3)") (class "Default")
      (node (ref "JP13") (pin "1") (pinfunction "1_1") (pintype "passive"))
      (node (ref "R30") (pin "2") (pinfunction "2_2") (pintype "passive"))
      (node (ref "U1") (pin "4") (pinfunction "~{MCLR/VPP/T1G/}SS1/RA3_4") (pintype "bidirectional"))
    )
    (net (code "124") (name "unconnected-(JP13-Pad6)") (class "Default")
      (node (ref "JP13") (pin "6") (pinfunction "6_6") (pintype "passive"))
    )
    (net (code "125") (name "unconnected-(JP16-Pad11)") (class "Default")
      (node (ref "JP16") (pin "11") (pinfunction "11_11") (pintype "passive"))
    )
    (net (code "126") (name "unconnected-(JP16-Pad12)") (class "Default")
      (node (ref "JP16") (pin "12") (pinfunction "12_12") (pintype "passive"))
    )
    (net (code "127") (name "unconnected-(JP16-Pad34)") (class "Default")
      (node (ref "JP16") (pin "34") (pinfunction "34_34") (pintype "passive"))
    )
    (net (code "128") (name "unconnected-(JP16-Pad36)") (class "Default")
      (node (ref "JP16") (pin "36") (pinfunction "36_36") (pintype "passive"))
    )
    (net (code "129") (name "unconnected-(JP16-Pad38)") (class "Default")
      (node (ref "JP16") (pin "38") (pinfunction "38_38") (pintype "passive"))
    )
    (net (code "130") (name "unconnected-(JP16-Pad40)") (class "Default")
      (node (ref "JP16") (pin "40") (pinfunction "40_40") (pintype "passive"))
    )
    (net (code "131") (name "unconnected-(JP16-Pad42)") (class "Default")
      (node (ref "JP16") (pin "42") (pinfunction "42_42") (pintype "passive"))
    )
    (net (code "132") (name "unconnected-(JP16-Pad44)") (class "Default")
      (node (ref "JP16") (pin "44") (pinfunction "44_44") (pintype "passive"))
    )
    (net (code "133") (name "unconnected-(JP16-Pad46)") (class "Default")
      (node (ref "JP16") (pin "46") (pinfunction "46_46") (pintype "passive"))
    )
    (net (code "134") (name "unconnected-(JP16-Pad48)") (class "Default")
      (node (ref "JP16") (pin "48") (pinfunction "48_48") (pintype "passive"))
    )
    (net (code "135") (name "unconnected-(JP17-Pad17)") (class "Default")
      (node (ref "JP17") (pin "17") (pinfunction "17_17") (pintype "passive"))
    )
    (net (code "136") (name "unconnected-(K1B-S-PadNO)") (class "Default")
      (node (ref "K1") (pin "NO") (pinfunction "S_NO") (pintype "passive"))
    )
    (net (code "137") (name "unconnected-(U1-CCP2{slash}P2A{slash}T1CKI{slash}T1OSI{slash}OSC1{slash}CLKIN{slash}RA5-Pad2)") (class "Default")
      (node (ref "U1") (pin "2") (pinfunction "CCP2/P2A/T1CKI/T1OSI/OSC1/CLKIN/RA5_2") (pintype "bidirectional"))
    )
    (net (code "138") (name "unconnected-(U1-RA2{slash}AN2{slash}CPS2{slash}T0CKI{slash}INT{slash}C1OUT{slash}SRQ{slash}CCP3{slash}FLT0-Pad11)") (class "Default")
      (node (ref "U1") (pin "11") (pinfunction "RA2/AN2/CPS2/T0CKI/INT/C1OUT/SRQ/CCP3/FLT0_11") (pintype "bidirectional"))
    )
    (net (code "139") (name "unconnected-(U1-RC2{slash}AN6{slash}CPS6{slash}C12IN2-{slash}P1D{slash}P2B{slash}SDO{slash}MDCIN1-Pad8)") (class "Default")
      (node (ref "U1") (pin "8") (pinfunction "RC2/AN6/CPS6/C12IN2-/P1D/P2B/SDO/MDCIN1_8") (pintype "bidirectional"))
    )
    (net (code "140") (name "unconnected-(U1-T1G{slash}P2B{slash}SDO{slash}CLKR{slash}T1OSO{slash}CLKOUT{slash}OSC2{slash}CPS3{slash}AN3{slash}RA4-Pad3)") (class "Default")
      (node (ref "U1") (pin "3") (pinfunction "T1G/P2B/SDO/CLKR/T1OSO/CLKOUT/OSC2/CPS3/AN3/RA4_3") (pintype "bidirectional"))
    )
  )
)
